# 7segement4digits1badidea-mk-2-smd.net
KiCad netlist of a schematic drawn in EAGLE
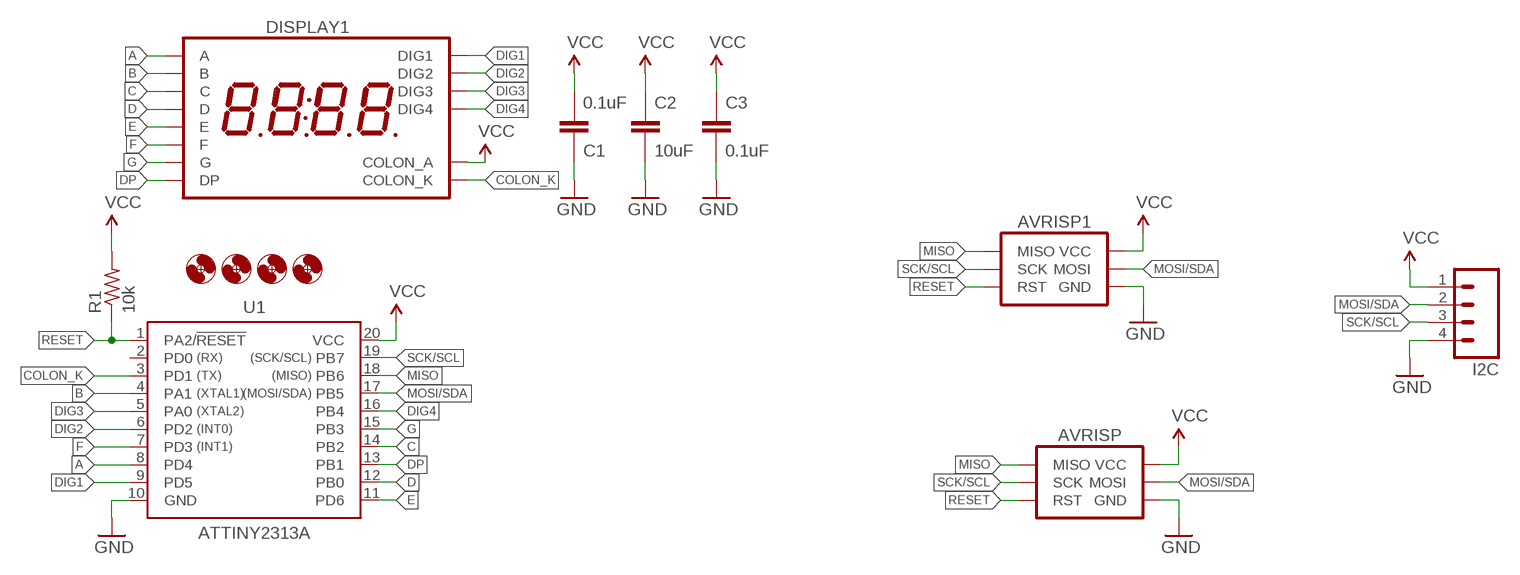
[diagram p0: schematic, sheet 1]

(export (version "E")
  (design (tool "Eeschema 10.0.6"))
  (components
    (comp (ref "AVRISP")
      (value "AVR_SPI_PRG_6PTH")
      (footprint "eagle-import:2X3")
      (libsource (lib "eagle-import") (part "AVR_SPI_PRG_6PTH"))
    )
    (comp (ref "AVRISP1")
      (value "AVR_SPI_PRG_6SMD-RA-FLOPPED-I2C")
      (footprint "eagle-import:1X06-SMD")
      (libsource (lib "eagle-import") (part "AVR_SPI_PRG_6SMD-RA-FLOPPED-I2C"))
    )
    (comp (ref "C1")
      (value "0.1uF")
      (footprint "eagle-import:C0805")
      (libsource (lib "eagle-import") (part "CAPACITOR-CERAMICC0805"))
    )
    (comp (ref "C2")
      (value "10uF")
      (footprint "eagle-import:C0805")
      (libsource (lib "eagle-import") (part "CAPACITOR-CERAMICC0805"))
    )
    (comp (ref "C3")
      (value "0.1uF")
      (footprint "eagle-import:C0805")
      (libsource (lib "eagle-import") (part "CAPACITOR-CERAMICC0805"))
    )
    (comp (ref "DISPLAY1")
      (value "7SED_4DIGIT_14MM14.2MM-CC")
      (footprint "eagle-import:7SEG_4DIG")
      (libsource (lib "eagle-import") (part "7SED_4DIGIT_14MM14.2MM-CC"))
    )
    (comp (ref "H1")
      (value "HOLE#2")
      (footprint "eagle-import:HOLE-#2")
      (libsource (lib "eagle-import") (part "HOLE#2"))
    )
    (comp (ref "H2")
      (value "HOLE#2")
      (footprint "eagle-import:HOLE-#2")
      (libsource (lib "eagle-import") (part "HOLE#2"))
    )
    (comp (ref "H3")
      (value "HOLE#2")
      (footprint "eagle-import:HOLE-#2")
      (libsource (lib "eagle-import") (part "HOLE#2"))
    )
    (comp (ref "H4")
      (value "HOLE#2")
      (footprint "eagle-import:HOLE-#2")
      (libsource (lib "eagle-import") (part "HOLE#2"))
    )
    (comp (ref "I2C")
      (value "M04PTH")
      (footprint "eagle-import:1X04-PTH-VERT")
      (libsource (lib "eagle-import") (part "M04PTH"))
    )
    (comp (ref "R1")
      (value "10k")
      (footprint "eagle-import:R0805")
      (libsource (lib "eagle-import") (part "RESISTORR0805"))
    )
    (comp (ref "U1")
      (value "ATTINY2313A")
      (footprint "eagle-import:SOP20W")
      (libsource (lib "eagle-import") (part "ATTINY2313ASOIC"))
    )
  )
  (nets
    (net (code "1") (name "A") (class "Default")
      (node (ref "DISPLAY1") (pin "P$13") (pinfunction "A_P$13") (pintype "passive"))
      (node (ref "U1") (pin "8") (pinfunction "PD4_8") (pintype "bidirectional"))
    )
    (net (code "2") (name "B") (class "Default")
      (node (ref "DISPLAY1") (pin "P$9") (pinfunction "B_P$9") (pintype "passive"))
      (node (ref "U1") (pin "4") (pinfunction "PA1_4") (pintype "bidirectional"))
    )
    (net (code "3") (name "C") (class "Default")
      (node (ref "DISPLAY1") (pin "P$4") (pinfunction "C_P$4") (pintype "passive"))
      (node (ref "U1") (pin "14") (pinfunction "PB2_14") (pintype "bidirectional"))
    )
    (net (code "4") (name "COLON_K") (class "Default")
      (node (ref "DISPLAY1") (pin "P$7") (pinfunction "COLON_K_P$7") (pintype "passive"))
      (node (ref "U1") (pin "3") (pinfunction "PD1_3") (pintype "bidirectional"))
    )
    (net (code "5") (name "D") (class "Default")
      (node (ref "DISPLAY1") (pin "P$2") (pinfunction "D_P$2") (pintype "passive"))
      (node (ref "U1") (pin "12") (pinfunction "PB0_12") (pintype "bidirectional"))
    )
    (net (code "6") (name "DIG1") (class "Default")
      (node (ref "DISPLAY1") (pin "P$14") (pinfunction "DIG1_P$14") (pintype "passive"))
      (node (ref "U1") (pin "9") (pinfunction "PD5_9") (pintype "bidirectional"))
    )
    (net (code "7") (name "DIG2") (class "Default")
      (node (ref "DISPLAY1") (pin "P$11") (pinfunction "DIG2_P$11") (pintype "passive"))
      (node (ref "U1") (pin "6") (pinfunction "PD2_6") (pintype "bidirectional"))
    )
    (net (code "8") (name "DIG3") (class "Default")
      (node (ref "DISPLAY1") (pin "P$10") (pinfunction "DIG3_P$10") (pintype "passive"))
      (node (ref "U1") (pin "5") (pinfunction "PA0_5") (pintype "bidirectional"))
    )
    (net (code "9") (name "DIG4") (class "Default")
      (node (ref "DISPLAY1") (pin "P$6") (pinfunction "DIG4_P$6") (pintype "passive"))
      (node (ref "U1") (pin "16") (pinfunction "PB4_16") (pintype "bidirectional"))
    )
    (net (code "10") (name "DP") (class "Default")
      (node (ref "DISPLAY1") (pin "P$3") (pinfunction "DP_P$3") (pintype "passive"))
      (node (ref "U1") (pin "13") (pinfunction "PB1_13") (pintype "bidirectional"))
    )
    (net (code "11") (name "E") (class "Default")
      (node (ref "DISPLAY1") (pin "P$1") (pinfunction "E_P$1") (pintype "passive"))
      (node (ref "U1") (pin "11") (pinfunction "PD6_11") (pintype "bidirectional"))
    )
    (net (code "12") (name "F") (class "Default")
      (node (ref "DISPLAY1") (pin "P$12") (pinfunction "F_P$12") (pintype "passive"))
      (node (ref "U1") (pin "7") (pinfunction "PD3_7") (pintype "bidirectional"))
    )
    (net (code "13") (name "G") (class "Default")
      (node (ref "DISPLAY1") (pin "P$5") (pinfunction "G_P$5") (pintype "passive"))
      (node (ref "U1") (pin "15") (pinfunction "PB3_15") (pintype "bidirectional"))
    )
    (net (code "14") (name "GND") (class "Default")
      (node (ref "AVRISP") (pin "6") (pinfunction "GND_6") (pintype "passive"))
      (node (ref "AVRISP1") (pin "4") (pinfunction "GND_4") (pintype "passive"))
      (node (ref "C1") (pin "1") (pinfunction "1_1") (pintype "passive"))
      (node (ref "C2") (pin "2") (pinfunction "2_2") (pintype "passive"))
      (node (ref "C3") (pin "2") (pinfunction "2_2") (pintype "passive"))
      (node (ref "I2C") (pin "4") (pinfunction "4_4") (pintype "passive"))
      (node (ref "U1") (pin "10") (pinfunction "GND_10") (pintype "bidirectional"))
    )
    (net (code "15") (name "MISO") (class "Default")
      (node (ref "AVRISP") (pin "1") (pinfunction "MISO_1") (pintype "passive"))
      (node (ref "AVRISP1") (pin "5") (pinfunction "MISO_5") (pintype "passive"))
      (node (ref "U1") (pin "18") (pinfunction "PB6_18") (pintype "bidirectional"))
    )
    (net (code "16") (name "MOSI{slash}SDA") (class "Default")
      (node (ref "AVRISP") (pin "4") (pinfunction "MOSI_4") (pintype "passive"))
      (node (ref "AVRISP1") (pin "3") (pinfunction "MOSI_3") (pintype "passive"))
      (node (ref "I2C") (pin "2") (pinfunction "2_2") (pintype "passive"))
      (node (ref "U1") (pin "17") (pinfunction "PB5_17") (pintype "bidirectional"))
    )
    (net (code "17") (name "RESET") (class "Default")
      (node (ref "AVRISP") (pin "5") (pinfunction "RST_5") (pintype "passive"))
      (node (ref "AVRISP1") (pin "6") (pinfunction "RST_6") (pintype "passive"))
      (node (ref "R1") (pin "1") (pinfunction "1_1") (pintype "passive"))
      (node (ref "U1") (pin "1") (pinfunction "PA2/~{RESET}_1") (pintype "bidirectional"))
    )
    (net (code "18") (name "SCK{slash}SCL") (class "Default")
      (node (ref "AVRISP") (pin "3") (pinfunction "SCK_3") (pintype "passive"))
      (node (ref "AVRISP1") (pin "2") (pinfunction "SCK_2") (pintype "passive"))
      (node (ref "I2C") (pin "3") (pinfunction "3_3") (pintype "passive"))
      (node (ref "U1") (pin "19") (pinfunction "PB7_19") (pintype "bidirectional"))
    )
    (net (code "19") (name "VCC") (class "Default")
      (node (ref "AVRISP") (pin "2") (pinfunction "VCC_2") (pintype "passive"))
      (node (ref "AVRISP1") (pin "1") (pinfunction "VCC_1") (pintype "passive"))
      (node (ref "C1") (pin "2") (pinfunction "2_2") (pintype "passive"))
      (node (ref "C2") (pin "1") (pinfunction "1_1") (pintype "passive"))
      (node (ref "C3") (pin "1") (pinfunction "1_1") (pintype "passive"))
      (node (ref "DISPLAY1") (pin "P$8") (pinfunction "COLON_A_P$8") (pintype "passive"))
      (node (ref "I2C") (pin "1") (pinfunction "1_1") (pintype "passive"))
      (node (ref "R1") (pin "2") (pinfunction "2_2") (pintype "passive"))
      (node (ref "U1") (pin "20") (pinfunction "VCC_20") (pintype "bidirectional"))
    )
    (net (code "20") (name "unconnected-(U1-PD0-Pad2)") (class "Default")
      (node (ref "U1") (pin "2") (pinfunction "PD0_2") (pintype "bidirectional"))
    )
  )
)
